# Sheet.net
KiCad netlist of a schematic drawn in Altium Designer
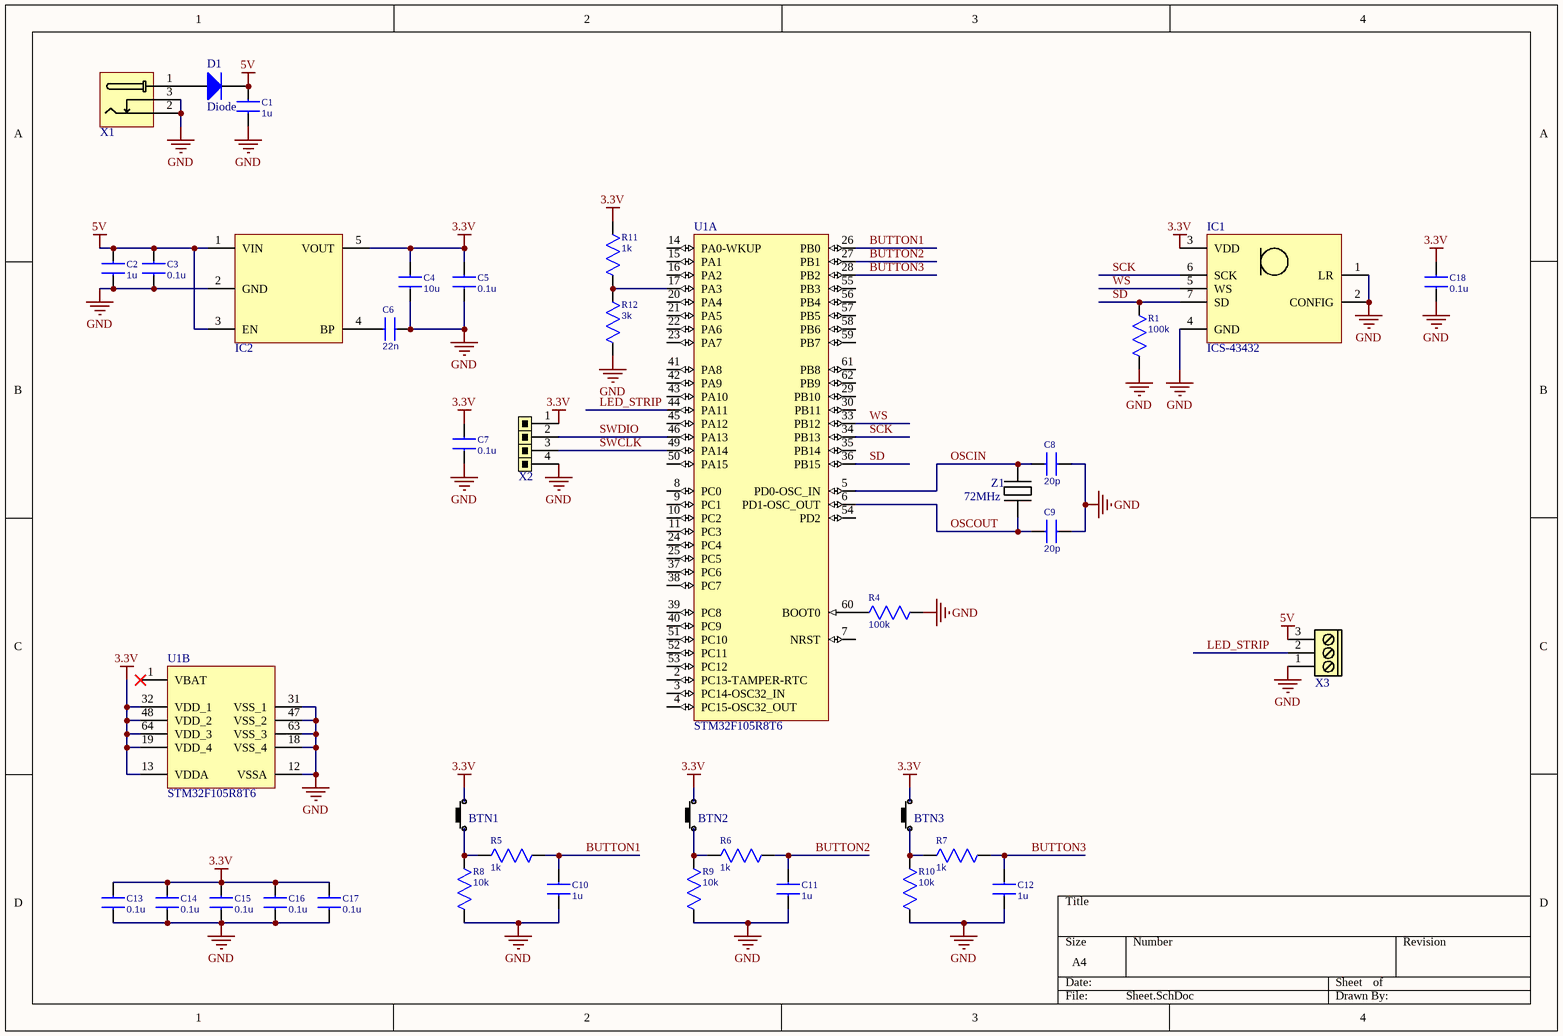
[diagram p0: Sheet.SchDoc]

(export (version "E")
  (design (tool "Eeschema 10.0.6"))
  (components
    (comp (ref "BTN1")
      (value "Push Button")
      (footprint "PUSH BUTTON")
      (description "Push button")
      (libsource (lib "Light_Music_Integrated_Library") (part "Push Button"))
    )
    (comp (ref "BTN2")
      (value "Push Button")
      (footprint "PUSH BUTTON")
      (description "Push button")
      (libsource (lib "Light_Music_Integrated_Library") (part "Push Button"))
    )
    (comp (ref "BTN3")
      (value "Push Button")
      (footprint "PUSH BUTTON")
      (description "Push button")
      (libsource (lib "Light_Music_Integrated_Library") (part "Push Button"))
    )
    (comp (ref "C1")
      (value "1u")
      (footprint "C_0805")
      (description "Capacitor")
      (libsource (lib "AX_Altium_v2.3") (part "C0805"))
    )
    (comp (ref "C2")
      (value "1u")
      (footprint "C_0805")
      (description "Capacitor")
      (libsource (lib "AX_Altium_v2.3") (part "C0805"))
    )
    (comp (ref "C3")
      (value "0.1u")
      (footprint "C_0603")
      (description "Capacitor")
      (libsource (lib "AX_Altium_v2.3") (part "C0603"))
    )
    (comp (ref "C4")
      (value "10u")
      (footprint "C_0805")
      (description "Capacitor")
      (libsource (lib "AX_Altium_v2.3") (part "C0805"))
    )
    (comp (ref "C5")
      (value "0.1u")
      (footprint "C_0603")
      (description "Capacitor")
      (libsource (lib "AX_Altium_v2.3") (part "C0603"))
    )
    (comp (ref "C6")
      (value "22n")
      (footprint "C_0603")
      (description "Capacitor")
      (libsource (lib "AX_Altium_v2.3") (part "C0603"))
    )
    (comp (ref "C7")
      (value "0.1u")
      (footprint "C_0603")
      (description "Capacitor")
      (libsource (lib "AX_Altium_v2.3") (part "C0603"))
    )
    (comp (ref "C8")
      (value "20p")
      (footprint "C_0603")
      (description "Capacitor")
      (libsource (lib "AX_Altium_v2.3") (part "C0603"))
    )
    (comp (ref "C9")
      (value "20p")
      (footprint "C_0603")
      (description "Capacitor")
      (libsource (lib "AX_Altium_v2.3") (part "C0603"))
    )
    (comp (ref "C10")
      (value "1u")
      (footprint "C_0603")
      (description "Capacitor")
      (libsource (lib "AX_Altium_v2.3") (part "C0603"))
    )
    (comp (ref "C11")
      (value "1u")
      (footprint "C_0603")
      (description "Capacitor")
      (libsource (lib "AX_Altium_v2.3") (part "C0603"))
    )
    (comp (ref "C12")
      (value "1u")
      (footprint "C_0603")
      (description "Capacitor")
      (libsource (lib "AX_Altium_v2.3") (part "C0603"))
    )
    (comp (ref "C13")
      (value "0.1u")
      (footprint "C_0603")
      (description "Capacitor")
      (libsource (lib "AX_Altium_v2.3") (part "C0603"))
    )
    (comp (ref "C14")
      (value "0.1u")
      (footprint "C_0603")
      (description "Capacitor")
      (libsource (lib "AX_Altium_v2.3") (part "C0603"))
    )
    (comp (ref "C15")
      (value "0.1u")
      (footprint "C_0603")
      (description "Capacitor")
      (libsource (lib "AX_Altium_v2.3") (part "C0603"))
    )
    (comp (ref "C16")
      (value "0.1u")
      (footprint "C_0603")
      (description "Capacitor")
      (libsource (lib "AX_Altium_v2.3") (part "C0603"))
    )
    (comp (ref "C17")
      (value "0.1u")
      (footprint "C_0603")
      (description "Capacitor")
      (libsource (lib "AX_Altium_v2.3") (part "C0603"))
    )
    (comp (ref "C18")
      (value "0.1u")
      (footprint "C_0603")
      (description "Capacitor")
      (libsource (lib "AX_Altium_v2.3") (part "C0603"))
    )
    (comp (ref "D1")
      (value "Diode")
      (footprint "SMC")
      (description "Default Diode")
      (fields (field (name "PUBLISHER") "Altium Limited"))
      (libsource (lib "Miscellaneous Devices") (part "Diode"))
    )
    (comp (ref "IC1")
      (value "ICS-43432")
      (footprint "ICS-43432")
      (description "Low-Noise Microphone with I2  S Digital Output")
      (libsource (lib "Light_Music_Integrated_Library") (part "ICS-43432"))
    )
    (comp (ref "IC2")
      (value "RT9193")
      (footprint "SOT23")
      (description "300mA, CMOS LDO Regulator")
      (libsource (lib "Light_Music_Integrated_Library") (part "RT9193"))
    )
    (comp (ref "R1")
      (value "100k")
      (footprint "R_0603")
      (description "Resistor")
      (libsource (lib "AX_Altium_v2.3") (part "R0603"))
    )
    (comp (ref "R4")
      (value "100k")
      (footprint "R_0603")
      (description "Resistor")
      (libsource (lib "AX_Altium_v2.3") (part "R0603"))
    )
    (comp (ref "R5")
      (value "1k")
      (footprint "R_0603")
      (description "Resistor")
      (libsource (lib "AX_Altium_v2.3") (part "R0603"))
    )
    (comp (ref "R6")
      (value "1k")
      (footprint "R_0603")
      (description "Resistor")
      (libsource (lib "AX_Altium_v2.3") (part "R0603"))
    )
    (comp (ref "R7")
      (value "1k")
      (footprint "R_0603")
      (description "Resistor")
      (libsource (lib "AX_Altium_v2.3") (part "R0603"))
    )
    (comp (ref "R8")
      (value "10k")
      (footprint "R_0603")
      (description "Resistor")
      (libsource (lib "AX_Altium_v2.3") (part "R0603"))
    )
    (comp (ref "R9")
      (value "10k")
      (footprint "R_0603")
      (description "Resistor")
      (libsource (lib "AX_Altium_v2.3") (part "R0603"))
    )
    (comp (ref "R10")
      (value "10k")
      (footprint "R_0603")
      (description "Resistor")
      (libsource (lib "AX_Altium_v2.3") (part "R0603"))
    )
    (comp (ref "R11")
      (value "1k")
      (footprint "R_0603")
      (description "Resistor")
      (libsource (lib "AX_Altium_v2.3") (part "R0603"))
    )
    (comp (ref "R12")
      (value "3k")
      (footprint "R_0603")
      (description "Resistor")
      (libsource (lib "AX_Altium_v2.3") (part "R0603"))
    )
    (comp (ref "U1")
      (value "STM32F105R8T6")
      (footprint "STM-LQFP64_N")
      (libsource (lib "STMicroelectronics STM32 F1") (part "STM32F105R8T6"))
    )
    (comp (ref "X1")
      (value "Jack Female")
      (footprint "DC-140")
      (libsource (lib "Light_Music_Integrated_Library") (part "Jack Female"))
    )
    (comp (ref "X2")
      (value "PLS-4")
      (footprint "PLS-4")
      (libsource (lib "Light_Music_Integrated_Library") (part "PLS-4"))
    )
    (comp (ref "X3")
      (value "DG-300-3")
      (footprint "YH-XH-3")
      (libsource (lib "Light_Music_Integrated_Library") (part "DG-300-3"))
    )
    (comp (ref "Z1")
      (value "72MHz")
      (footprint "HC-49")
      (description "Quartz resonator")
      (libsource (lib "Light_Music_Integrated_Library") (part "XTAL"))
    )
  )
  (nets
    (net (code "1") (name "/BUTTON1") (class "Default")
      (node (ref "C10") (pin "2") (pintype "passive"))
      (node (ref "R5") (pin "2") (pintype "passive"))
      (node (ref "U1") (pin "26") (pinfunction "PB0_26") (pintype "bidirectional"))
    )
    (net (code "2") (name "/BUTTON2") (class "Default")
      (node (ref "C11") (pin "2") (pintype "passive"))
      (node (ref "R6") (pin "2") (pintype "passive"))
      (node (ref "U1") (pin "27") (pinfunction "PB1_27") (pintype "bidirectional"))
    )
    (net (code "3") (name "/BUTTON3") (class "Default")
      (node (ref "C12") (pin "2") (pintype "passive"))
      (node (ref "R7") (pin "2") (pintype "passive"))
      (node (ref "U1") (pin "28") (pinfunction "PB2_28") (pintype "bidirectional"))
    )
    (net (code "4") (name "/LED_STRIP") (class "Default")
      (node (ref "U1") (pin "44") (pinfunction "PA11_44") (pintype "bidirectional"))
      (node (ref "X3") (pin "2") (pinfunction "2_2") (pintype "passive"))
    )
    (net (code "5") (name "/OSCIN") (class "Default")
      (node (ref "C8") (pin "2") (pintype "passive"))
      (node (ref "U1") (pin "5") (pinfunction "PD0-OSC_IN_5") (pintype "bidirectional"))
      (node (ref "Z1") (pin "2") (pinfunction "2_2") (pintype "passive"))
    )
    (net (code "6") (name "/OSCOUT") (class "Default")
      (node (ref "C9") (pin "2") (pintype "passive"))
      (node (ref "U1") (pin "6") (pinfunction "PD1-OSC_OUT_6") (pintype "bidirectional"))
      (node (ref "Z1") (pin "1") (pinfunction "1_1") (pintype "passive"))
    )
    (net (code "7") (name "/SCK") (class "Default")
      (node (ref "IC1") (pin "6") (pinfunction "SCK_6") (pintype "passive"))
      (node (ref "U1") (pin "34") (pinfunction "PB13_34") (pintype "bidirectional"))
    )
    (net (code "8") (name "/SD") (class "Default")
      (node (ref "IC1") (pin "7") (pinfunction "SD_7") (pintype "passive"))
      (node (ref "R1") (pin "1") (pintype "passive"))
      (node (ref "U1") (pin "36") (pinfunction "PB15_36") (pintype "bidirectional"))
    )
    (net (code "9") (name "/SWCLK") (class "Default")
      (node (ref "U1") (pin "49") (pinfunction "PA14_49") (pintype "bidirectional"))
      (node (ref "X2") (pin "3") (pinfunction "3_3") (pintype "passive"))
    )
    (net (code "10") (name "/SWDIO") (class "Default")
      (node (ref "U1") (pin "46") (pinfunction "PA13_46") (pintype "bidirectional"))
      (node (ref "X2") (pin "2") (pinfunction "2_2") (pintype "passive"))
    )
    (net (code "11") (name "/WS") (class "Default")
      (node (ref "IC1") (pin "5") (pinfunction "WS_5") (pintype "passive"))
      (node (ref "U1") (pin "33") (pinfunction "PB12_33") (pintype "bidirectional"))
    )
    (net (code "12") (name "3.3V") (class "Default")
      (node (ref "BTN1") (pin "2") (pinfunction "2_2") (pintype "passive"))
      (node (ref "BTN2") (pin "2") (pinfunction "2_2") (pintype "passive"))
      (node (ref "BTN3") (pin "2") (pinfunction "2_2") (pintype "passive"))
      (node (ref "C13") (pin "1") (pintype "passive"))
      (node (ref "C14") (pin "1") (pintype "passive"))
      (node (ref "C15") (pin "1") (pintype "passive"))
      (node (ref "C16") (pin "1") (pintype "passive"))
      (node (ref "C17") (pin "1") (pintype "passive"))
      (node (ref "C18") (pin "1") (pintype "passive"))
      (node (ref "C4") (pin "2") (pintype "passive"))
      (node (ref "C5") (pin "1") (pintype "passive"))
      (node (ref "C7") (pin "1") (pintype "passive"))
      (node (ref "IC1") (pin "3") (pinfunction "VDD_3") (pintype "passive"))
      (node (ref "IC2") (pin "5") (pinfunction "VOUT_5") (pintype "passive"))
      (node (ref "R11") (pin "2") (pintype "passive"))
      (node (ref "U1") (pin "13") (pinfunction "VDDA_13") (pintype "power_in"))
      (node (ref "U1") (pin "19") (pinfunction "VDD_4_19") (pintype "power_in"))
      (node (ref "U1") (pin "32") (pinfunction "VDD_1_32") (pintype "power_in"))
      (node (ref "U1") (pin "48") (pinfunction "VDD_2_48") (pintype "power_in"))
      (node (ref "U1") (pin "64") (pinfunction "VDD_3_64") (pintype "power_in"))
      (node (ref "X2") (pin "1") (pinfunction "1_1") (pintype "passive"))
    )
    (net (code "13") (name "5V") (class "Default")
      (node (ref "C1") (pin "2") (pintype "passive"))
      (node (ref "C2") (pin "2") (pintype "passive"))
      (node (ref "C3") (pin "2") (pintype "passive"))
      (node (ref "D1") (pin "2") (pinfunction "K_2") (pintype "passive"))
      (node (ref "IC2") (pin "1") (pinfunction "VIN_1") (pintype "passive"))
      (node (ref "IC2") (pin "3") (pinfunction "EN_3") (pintype "passive"))
      (node (ref "X3") (pin "3") (pinfunction "3_3") (pintype "passive"))
    )
    (net (code "14") (name "GND") (class "Default")
      (node (ref "C1") (pin "1") (pintype "passive"))
      (node (ref "C10") (pin "1") (pintype "passive"))
      (node (ref "C11") (pin "1") (pintype "passive"))
      (node (ref "C12") (pin "1") (pintype "passive"))
      (node (ref "C13") (pin "2") (pintype "passive"))
      (node (ref "C14") (pin "2") (pintype "passive"))
      (node (ref "C15") (pin "2") (pintype "passive"))
      (node (ref "C16") (pin "2") (pintype "passive"))
      (node (ref "C17") (pin "2") (pintype "passive"))
      (node (ref "C18") (pin "2") (pintype "passive"))
      (node (ref "C2") (pin "1") (pintype "passive"))
      (node (ref "C3") (pin "1") (pintype "passive"))
      (node (ref "C4") (pin "1") (pintype "passive"))
      (node (ref "C5") (pin "2") (pintype "passive"))
      (node (ref "C6") (pin "2") (pintype "passive"))
      (node (ref "C7") (pin "2") (pintype "passive"))
      (node (ref "C8") (pin "1") (pintype "passive"))
      (node (ref "C9") (pin "1") (pintype "passive"))
      (node (ref "IC1") (pin "1") (pinfunction "LR_1") (pintype "passive"))
      (node (ref "IC1") (pin "2") (pinfunction "CONFIG_2") (pintype "passive"))
      (node (ref "IC1") (pin "4") (pinfunction "GND_4") (pintype "passive"))
      (node (ref "IC2") (pin "2") (pinfunction "GND_2") (pintype "passive"))
      (node (ref "R1") (pin "2") (pintype "passive"))
      (node (ref "R10") (pin "1") (pintype "passive"))
      (node (ref "R12") (pin "1") (pintype "passive"))
      (node (ref "R4") (pin "1") (pintype "passive"))
      (node (ref "R8") (pin "1") (pintype "passive"))
      (node (ref "R9") (pin "1") (pintype "passive"))
      (node (ref "U1") (pin "12") (pinfunction "VSSA_12") (pintype "power_in"))
      (node (ref "U1") (pin "18") (pinfunction "VSS_4_18") (pintype "power_in"))
      (node (ref "U1") (pin "31") (pinfunction "VSS_1_31") (pintype "power_in"))
      (node (ref "U1") (pin "47") (pinfunction "VSS_2_47") (pintype "power_in"))
      (node (ref "U1") (pin "63") (pinfunction "VSS_3_63") (pintype "power_in"))
      (node (ref "X1") (pin "2") (pinfunction "2_2") (pintype "passive"))
      (node (ref "X1") (pin "3") (pinfunction "3_3") (pintype "passive"))
      (node (ref "X2") (pin "4") (pinfunction "4_4") (pintype "passive"))
      (node (ref "X3") (pin "1") (pinfunction "1_1") (pintype "passive"))
    )
    (net (code "15") (name "Net-(BTN1-Pad1)") (class "Default")
      (node (ref "BTN1") (pin "1") (pinfunction "1_1") (pintype "passive"))
      (node (ref "R5") (pin "1") (pintype "passive"))
      (node (ref "R8") (pin "2") (pintype "passive"))
    )
    (net (code "16") (name "Net-(BTN2-Pad1)") (class "Default")
      (node (ref "BTN2") (pin "1") (pinfunction "1_1") (pintype "passive"))
      (node (ref "R6") (pin "1") (pintype "passive"))
      (node (ref "R9") (pin "2") (pintype "passive"))
    )
    (net (code "17") (name "Net-(BTN3-Pad1)") (class "Default")
      (node (ref "BTN3") (pin "1") (pinfunction "1_1") (pintype "passive"))
      (node (ref "R10") (pin "2") (pintype "passive"))
      (node (ref "R7") (pin "1") (pintype "passive"))
    )
    (net (code "18") (name "Net-(D1-A)") (class "Default")
      (node (ref "D1") (pin "1") (pinfunction "A_1") (pintype "passive"))
      (node (ref "X1") (pin "1") (pinfunction "1_1") (pintype "passive"))
    )
    (net (code "19") (name "Net-(IC2-BP)") (class "Default")
      (node (ref "C6") (pin "1") (pintype "passive"))
      (node (ref "IC2") (pin "4") (pinfunction "BP_4") (pintype "passive"))
    )
    (net (code "20") (name "Net-(U1A-BOOT0)") (class "Default")
      (node (ref "R4") (pin "2") (pintype "passive"))
      (node (ref "U1") (pin "60") (pinfunction "BOOT0_60") (pintype "input"))
    )
    (net (code "21") (name "Net-(U1A-PA3)") (class "Default")
      (node (ref "R11") (pin "1") (pintype "passive"))
      (node (ref "R12") (pin "2") (pintype "passive"))
      (node (ref "U1") (pin "17") (pinfunction "PA3_17") (pintype "bidirectional"))
    )
    (net (code "22") (name "unconnected-(U1A-NRST-Pad7)") (class "Default")
      (node (ref "U1") (pin "7") (pinfunction "NRST_7") (pintype "bidirectional"))
    )
    (net (code "23") (name "unconnected-(U1A-PA0-WKUP-Pad14)") (class "Default")
      (node (ref "U1") (pin "14") (pinfunction "PA0-WKUP_14") (pintype "bidirectional"))
    )
    (net (code "24") (name "unconnected-(U1A-PA1-Pad15)") (class "Default")
      (node (ref "U1") (pin "15") (pinfunction "PA1_15") (pintype "bidirectional"))
    )
    (net (code "25") (name "unconnected-(U1A-PA2-Pad16)") (class "Default")
      (node (ref "U1") (pin "16") (pinfunction "PA2_16") (pintype "bidirectional"))
    )
    (net (code "26") (name "unconnected-(U1A-PA4-Pad20)") (class "Default")
      (node (ref "U1") (pin "20") (pinfunction "PA4_20") (pintype "bidirectional"))
    )
    (net (code "27") (name "unconnected-(U1A-PA5-Pad21)") (class "Default")
      (node (ref "U1") (pin "21") (pinfunction "PA5_21") (pintype "bidirectional"))
    )
    (net (code "28") (name "unconnected-(U1A-PA6-Pad22)") (class "Default")
      (node (ref "U1") (pin "22") (pinfunction "PA6_22") (pintype "bidirectional"))
    )
    (net (code "29") (name "unconnected-(U1A-PA7-Pad23)") (class "Default")
      (node (ref "U1") (pin "23") (pinfunction "PA7_23") (pintype "bidirectional"))
    )
    (net (code "30") (name "unconnected-(U1A-PA8-Pad41)") (class "Default")
      (node (ref "U1") (pin "41") (pinfunction "PA8_41") (pintype "bidirectional"))
    )
    (net (code "31") (name "unconnected-(U1A-PA9-Pad42)") (class "Default")
      (node (ref "U1") (pin "42") (pinfunction "PA9_42") (pintype "bidirectional"))
    )
    (net (code "32") (name "unconnected-(U1A-PA10-Pad43)") (class "Default")
      (node (ref "U1") (pin "43") (pinfunction "PA10_43") (pintype "bidirectional"))
    )
    (net (code "33") (name "unconnected-(U1A-PA12-Pad45)") (class "Default")
      (node (ref "U1") (pin "45") (pinfunction "PA12_45") (pintype "bidirectional"))
    )
    (net (code "34") (name "unconnected-(U1A-PA15-Pad50)") (class "Default")
      (node (ref "U1") (pin "50") (pinfunction "PA15_50") (pintype "bidirectional"))
    )
    (net (code "35") (name "unconnected-(U1A-PB3-Pad55)") (class "Default")
      (node (ref "U1") (pin "55") (pinfunction "PB3_55") (pintype "bidirectional"))
    )
    (net (code "36") (name "unconnected-(U1A-PB4-Pad56)") (class "Default")
      (node (ref "U1") (pin "56") (pinfunction "PB4_56") (pintype "bidirectional"))
    )
    (net (code "37") (name "unconnected-(U1A-PB5-Pad57)") (class "Default")
      (node (ref "U1") (pin "57") (pinfunction "PB5_57") (pintype "bidirectional"))
    )
    (net (code "38") (name "unconnected-(U1A-PB6-Pad58)") (class "Default")
      (node (ref "U1") (pin "58") (pinfunction "PB6_58") (pintype "bidirectional"))
    )
    (net (code "39") (name "unconnected-(U1A-PB7-Pad59)") (class "Default")
      (node (ref "U1") (pin "59") (pinfunction "PB7_59") (pintype "bidirectional"))
    )
    (net (code "40") (name "unconnected-(U1A-PB8-Pad61)") (class "Default")
      (node (ref "U1") (pin "61") (pinfunction "PB8_61") (pintype "bidirectional"))
    )
    (net (code "41") (name "unconnected-(U1A-PB9-Pad62)") (class "Default")
      (node (ref "U1") (pin "62") (pinfunction "PB9_62") (pintype "bidirectional"))
    )
    (net (code "42") (name "unconnected-(U1A-PB10-Pad29)") (class "Default")
      (node (ref "U1") (pin "29") (pinfunction "PB10_29") (pintype "bidirectional"))
    )
    (net (code "43") (name "unconnected-(U1A-PB11-Pad30)") (class "Default")
      (node (ref "U1") (pin "30") (pinfunction "PB11_30") (pintype "bidirectional"))
    )
    (net (code "44") (name "unconnected-(U1A-PB14-Pad35)") (class "Default")
      (node (ref "U1") (pin "35") (pinfunction "PB14_35") (pintype "bidirectional"))
    )
    (net (code "45") (name "unconnected-(U1A-PC0-Pad8)") (class "Default")
      (node (ref "U1") (pin "8") (pinfunction "PC0_8") (pintype "bidirectional"))
    )
    (net (code "46") (name "unconnected-(U1A-PC1-Pad9)") (class "Default")
      (node (ref "U1") (pin "9") (pinfunction "PC1_9") (pintype "bidirectional"))
    )
    (net (code "47") (name "unconnected-(U1A-PC2-Pad10)") (class "Default")
      (node (ref "U1") (pin "10") (pinfunction "PC2_10") (pintype "bidirectional"))
    )
    (net (code "48") (name "unconnected-(U1A-PC3-Pad11)") (class "Default")
      (node (ref "U1") (pin "11") (pinfunction "PC3_11") (pintype "bidirectional"))
    )
    (net (code "49") (name "unconnected-(U1A-PC4-Pad24)") (class "Default")
      (node (ref "U1") (pin "24") (pinfunction "PC4_24") (pintype "bidirectional"))
    )
    (net (code "50") (name "unconnected-(U1A-PC5-Pad25)") (class "Default")
      (node (ref "U1") (pin "25") (pinfunction "PC5_25") (pintype "bidirectional"))
    )
    (net (code "51") (name "unconnected-(U1A-PC6-Pad37)") (class "Default")
      (node (ref "U1") (pin "37") (pinfunction "PC6_37") (pintype "bidirectional"))
    )
    (net (code "52") (name "unconnected-(U1A-PC7-Pad38)") (class "Default")
      (node (ref "U1") (pin "38") (pinfunction "PC7_38") (pintype "bidirectional"))
    )
    (net (code "53") (name "unconnected-(U1A-PC8-Pad39)") (class "Default")
      (node (ref "U1") (pin "39") (pinfunction "PC8_39") (pintype "bidirectional"))
    )
    (net (code "54") (name "unconnected-(U1A-PC9-Pad40)") (class "Default")
      (node (ref "U1") (pin "40") (pinfunction "PC9_40") (pintype "bidirectional"))
    )
    (net (code "55") (name "unconnected-(U1A-PC10-Pad51)") (class "Default")
      (node (ref "U1") (pin "51") (pinfunction "PC10_51") (pintype "bidirectional"))
    )
    (net (code "56") (name "unconnected-(U1A-PC11-Pad52)") (class "Default")
      (node (ref "U1") (pin "52") (pinfunction "PC11_52") (pintype "bidirectional"))
    )
    (net (code "57") (name "unconnected-(U1A-PC12-Pad53)") (class "Default")
      (node (ref "U1") (pin "53") (pinfunction "PC12_53") (pintype "bidirectional"))
    )
    (net (code "58") (name "unconnected-(U1A-PC13-TAMPER-RTC-Pad2)") (class "Default")
      (node (ref "U1") (pin "2") (pinfunction "PC13-TAMPER-RTC_2") (pintype "bidirectional"))
    )
    (net (code "59") (name "unconnected-(U1A-PC14-OSC32_IN-Pad3)") (class "Default")
      (node (ref "U1") (pin "3") (pinfunction "PC14-OSC32_IN_3") (pintype "bidirectional"))
    )
    (net (code "60") (name "unconnected-(U1A-PC15-OSC32_OUT-Pad4)") (class "Default")
      (node (ref "U1") (pin "4") (pinfunction "PC15-OSC32_OUT_4") (pintype "bidirectional"))
    )
    (net (code "61") (name "unconnected-(U1A-PD2-Pad54)") (class "Default")
      (node (ref "U1") (pin "54") (pinfunction "PD2_54") (pintype "bidirectional"))
    )
    (net (code "62") (name "unconnected-(U1B-VBAT-Pad1)") (class "Default")
      (node (ref "U1") (pin "1") (pinfunction "VBAT_1") (pintype "power_in+no_connect"))
    )
  )
)
